# Schematic.net
KiCad netlist of a schematic drawn in EAGLE
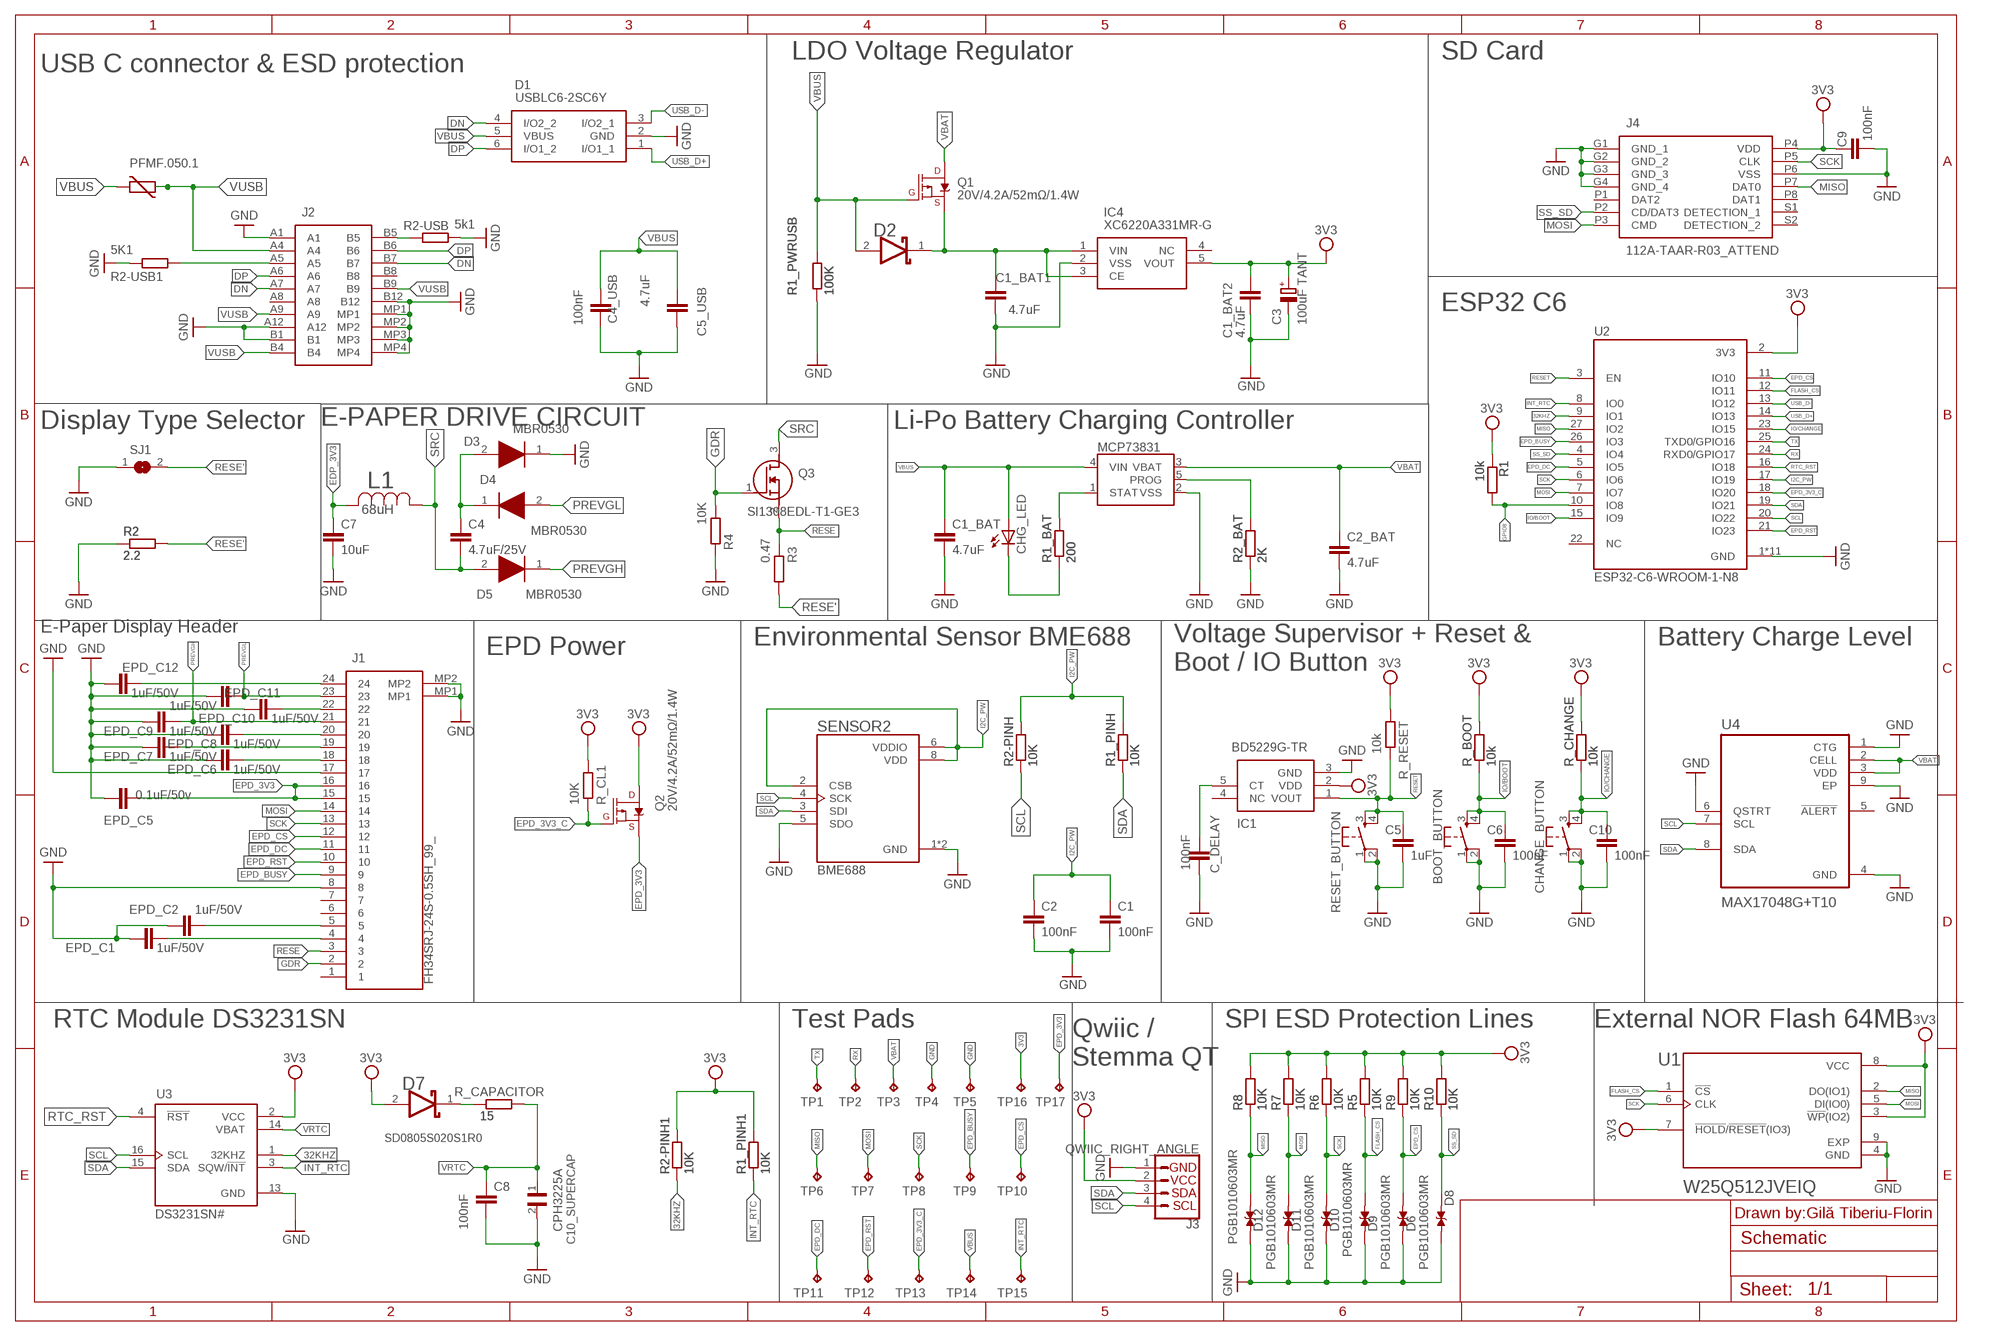
[diagram p0: schematic, sheet 1]

(export (version "E")
  (design (tool "Eeschema 10.0.6"))
  (components
    (comp (ref "BOOT_BUTTON")
      (value "BUTTON_CUSYOMV1")
      (footprint "eagle-import:MYBUTTON")
      (libsource (lib "eagle-import") (part "BUTTON_CUSYOMV1"))
    )
    (comp (ref "C1")
      (value "100nF")
      (footprint "eagle-import:EAGLE-LTSPICE_C0402")
      (libsource (lib "eagle-import") (part "EAGLE-LTSPICE_CC0402"))
    )
    (comp (ref "C1_BAT")
      (value "4.7uF")
      (footprint "eagle-import:EAGLE-LTSPICE_C0402")
      (libsource (lib "eagle-import") (part "EAGLE-LTSPICE_CC0402"))
    )
    (comp (ref "C1_BAT1")
      (value "4.7uF")
      (footprint "eagle-import:ESP32_WROVER_EAGLE-LTSPICE_C0402")
      (libsource (lib "eagle-import") (part "ESP32_WROVER_EAGLE-LTSPICE_CC0402"))
    )
    (comp (ref "C1_BAT2")
      (value "4.7uF")
      (footprint "eagle-import:ESP32_WROVER_EAGLE-LTSPICE_C0402")
      (libsource (lib "eagle-import") (part "ESP32_WROVER_EAGLE-LTSPICE_CC0402"))
    )
    (comp (ref "C2")
      (value "100nF")
      (footprint "eagle-import:EAGLE-LTSPICE_C0402")
      (libsource (lib "eagle-import") (part "EAGLE-LTSPICE_CC0402"))
    )
    (comp (ref "C2_BAT")
      (value "4.7uF")
      (footprint "eagle-import:EAGLE-LTSPICE_C0402")
      (libsource (lib "eagle-import") (part "EAGLE-LTSPICE_CC0402"))
    )
    (comp (ref "C3")
      (value "100uF TANT")
      (footprint "eagle-import:RCL_CT3528")
      (libsource (lib "eagle-import") (part "RCL_CPOL-EUCT3528"))
    )
    (comp (ref "C4")
      (value "4.7uF/25V")
      (footprint "eagle-import:EAGLE-LTSPICE_C0402")
      (libsource (lib "eagle-import") (part "EAGLE-LTSPICE_CC0402"))
    )
    (comp (ref "C4_USB")
      (value "100nF")
      (footprint "eagle-import:EAGLE-LTSPICE_C0402")
      (libsource (lib "eagle-import") (part "EAGLE-LTSPICE_CC0402"))
    )
    (comp (ref "C5")
      (value "1uF")
      (footprint "eagle-import:EAGLE-LTSPICE_C0402")
      (libsource (lib "eagle-import") (part "EAGLE-LTSPICE_CC0402"))
    )
    (comp (ref "C5_USB")
      (value "4.7uF")
      (footprint "eagle-import:EAGLE-LTSPICE_C0402")
      (libsource (lib "eagle-import") (part "EAGLE-LTSPICE_CC0402"))
    )
    (comp (ref "C6")
      (value "100nF")
      (footprint "eagle-import:EAGLE-LTSPICE_C0402")
      (libsource (lib "eagle-import") (part "EAGLE-LTSPICE_CC0402"))
    )
    (comp (ref "C7")
      (value "10uF")
      (footprint "eagle-import:EAGLE-LTSPICE_C0402")
      (libsource (lib "eagle-import") (part "EAGLE-LTSPICE_CC0402"))
    )
    (comp (ref "C8")
      (value "100nF")
      (footprint "eagle-import:EAGLE-LTSPICE_C0402")
      (libsource (lib "eagle-import") (part "EAGLE-LTSPICE_CC0402"))
    )
    (comp (ref "C9")
      (value "100nF")
      (footprint "eagle-import:EAGLE-LTSPICE_C0402")
      (libsource (lib "eagle-import") (part "EAGLE-LTSPICE_CC0402"))
    )
    (comp (ref "C10")
      (value "100nF")
      (footprint "eagle-import:EAGLE-LTSPICE_C0402")
      (libsource (lib "eagle-import") (part "EAGLE-LTSPICE_CC0402"))
    )
    (comp (ref "C11")
      (value "CPH3225A")
      (footprint "eagle-import:CAPCP3225X100N")
      (fields (field (name "MF") "Seiko Instruments"))
      (libsource (lib "eagle-import") (part "CPH3225A"))
    )
    (comp (ref "CHANGE_BUTTON")
      (value "BUTTON_CUSYOMV1")
      (footprint "eagle-import:MYBUTTON")
      (libsource (lib "eagle-import") (part "BUTTON_CUSYOMV1"))
    )
    (comp (ref "CHG_LED")
      (value "ADAFRUIT_LEDCHIP-LED0603")
      (footprint "eagle-import:ADAFRUIT_CHIP-LED0603")
      (libsource (lib "eagle-import") (part "ADAFRUIT_LEDCHIP-LED0603"))
    )
    (comp (ref "C_DELAY")
      (value "100nF")
      (footprint "eagle-import:EAGLE-LTSPICE_C0402")
      (libsource (lib "eagle-import") (part "EAGLE-LTSPICE_CC0402"))
    )
    (comp (ref "D1")
      (value "USBLC6-2SC6Y")
      (footprint "eagle-import:SOT95P280X145-6N")
      (fields (field (name "MF") "STMicroelectronics"))
      (libsource (lib "eagle-import") (part "USBLC6-2SC6Y"))
    )
    (comp (ref "D2")
      (value "ESP32_WROVER_AVX---SD0805S020S1R0_AVX_SD0805S020S1R0_0_0AVX_SD0805S020S1R0_0_0")
      (footprint "eagle-import:ESP32_WROVER_AVX---SD0805S020S1R0_AVX_SD0805S020S1R0_0")
      (fields
        (field (name "DIGIKEY_PART_NUMBER") "478-7800-1-ND")
        (field (name "MF") "AVX")
        (field (name "MOUSER_PART_NUMBER") "581-SD0805S020S1R0")
      )
      (libsource (lib "eagle-import") (part "ESP32_WROVER_AVX---SD0805S020S1R0_AVX_SD0805S020S1R0_0_0AVX_SD0805S020S1R0_0_0"))
    )
    (comp (ref "D3")
      (value "MBR0530")
      (footprint "eagle-import:SOD3716X135N")
      (fields (field (name "MF") "ON Semiconductor"))
      (libsource (lib "eagle-import") (part "MBR0530"))
    )
    (comp (ref "D4")
      (value "MBR0530")
      (footprint "eagle-import:SOD3716X135N")
      (fields (field (name "MF") "ON Semiconductor"))
      (libsource (lib "eagle-import") (part "MBR0530"))
    )
    (comp (ref "D5")
      (value "MBR0530")
      (footprint "eagle-import:SOD3716X135N")
      (fields (field (name "MF") "ON Semiconductor"))
      (libsource (lib "eagle-import") (part "MBR0530"))
    )
    (comp (ref "D6")
      (value "PGB1010603MR")
      (footprint "eagle-import:DIOC1608X36N")
      (fields (field (name "MF") "Littelfuse Inc."))
      (libsource (lib "eagle-import") (part "PGB1010603MR"))
    )
    (comp (ref "D7")
      (value "ESP32_WROVER_AVX---SD0805S020S1R0_AVX_SD0805S020S1R0_0_0AVX_SD0805S020S1R0_0_0")
      (footprint "eagle-import:ESP32_WROVER_AVX---SD0805S020S1R0_AVX_SD0805S020S1R0_0")
      (fields
        (field (name "DIGIKEY_PART_NUMBER") "478-7800-1-ND")
        (field (name "MF") "AVX")
        (field (name "MOUSER_PART_NUMBER") "581-SD0805S020S1R0")
      )
      (libsource (lib "eagle-import") (part "ESP32_WROVER_AVX---SD0805S020S1R0_AVX_SD0805S020S1R0_0_0AVX_SD0805S020S1R0_0_0"))
    )
    (comp (ref "D8")
      (value "PGB1010603MR")
      (footprint "eagle-import:DIOC1608X36N")
      (fields (field (name "MF") "Littelfuse Inc."))
      (libsource (lib "eagle-import") (part "PGB1010603MR"))
    )
    (comp (ref "D9")
      (value "PGB1010603MR")
      (footprint "eagle-import:DIOC1608X36N")
      (fields (field (name "MF") "Littelfuse Inc."))
      (libsource (lib "eagle-import") (part "PGB1010603MR"))
    )
    (comp (ref "D10")
      (value "PGB1010603MR")
      (footprint "eagle-import:DIOC1608X36N")
      (fields (field (name "MF") "Littelfuse Inc."))
      (libsource (lib "eagle-import") (part "PGB1010603MR"))
    )
    (comp (ref "D11")
      (value "PGB1010603MR")
      (footprint "eagle-import:DIOC1608X36N")
      (fields (field (name "MF") "Littelfuse Inc."))
      (libsource (lib "eagle-import") (part "PGB1010603MR"))
    )
    (comp (ref "D12")
      (value "PGB1010603MR")
      (footprint "eagle-import:DIOC1608X36N")
      (fields (field (name "MF") "Littelfuse Inc."))
      (libsource (lib "eagle-import") (part "PGB1010603MR"))
    )
    (comp (ref "EPD_C1")
      (value "1uF/50V")
      (footprint "eagle-import:EAGLE-LTSPICE_C0402")
      (libsource (lib "eagle-import") (part "EAGLE-LTSPICE_CC0402"))
    )
    (comp (ref "EPD_C2")
      (value "1uF/50V")
      (footprint "eagle-import:EAGLE-LTSPICE_C0402")
      (libsource (lib "eagle-import") (part "EAGLE-LTSPICE_CC0402"))
    )
    (comp (ref "EPD_C5")
      (value "0.1uF/50v")
      (footprint "eagle-import:EAGLE-LTSPICE_C0402")
      (libsource (lib "eagle-import") (part "EAGLE-LTSPICE_CC0402"))
    )
    (comp (ref "EPD_C6")
      (value "1uF/50V")
      (footprint "eagle-import:EAGLE-LTSPICE_C0402")
      (libsource (lib "eagle-import") (part "EAGLE-LTSPICE_CC0402"))
    )
    (comp (ref "EPD_C7")
      (value "1uF/50V")
      (footprint "eagle-import:EAGLE-LTSPICE_C0402")
      (libsource (lib "eagle-import") (part "EAGLE-LTSPICE_CC0402"))
    )
    (comp (ref "EPD_C8")
      (value "1uF/50V")
      (footprint "eagle-import:EAGLE-LTSPICE_C0402")
      (libsource (lib "eagle-import") (part "EAGLE-LTSPICE_CC0402"))
    )
    (comp (ref "EPD_C9")
      (value "1uF/50V")
      (footprint "eagle-import:EAGLE-LTSPICE_C0402")
      (libsource (lib "eagle-import") (part "EAGLE-LTSPICE_CC0402"))
    )
    (comp (ref "EPD_C10")
      (value "1uF/50V")
      (footprint "eagle-import:EAGLE-LTSPICE_C0402")
      (libsource (lib "eagle-import") (part "EAGLE-LTSPICE_CC0402"))
    )
    (comp (ref "EPD_C11")
      (value "1uF/50V")
      (footprint "eagle-import:EAGLE-LTSPICE_C0402")
      (libsource (lib "eagle-import") (part "EAGLE-LTSPICE_CC0402"))
    )
    (comp (ref "EPD_C12")
      (value "1uF/50V")
      (footprint "eagle-import:EAGLE-LTSPICE_C0402")
      (libsource (lib "eagle-import") (part "EAGLE-LTSPICE_CC0402"))
    )
    (comp (ref "IC1")
      (value "BD5229G-TR")
      (footprint "eagle-import:SOT95P280X125-5N")
      (fields (field (name "MOUSER_PART_NUMBER") "755-BD5229G-TR"))
      (libsource (lib "eagle-import") (part "BD5229G-TR"))
    )
    (comp (ref "IC4")
      (value "XC6220A331MR-G")
      (footprint "eagle-import:SOT95P280X120-5N")
      (fields (field (name "MOUSER_PART_NUMBER") "865-XC6220A331MR-G"))
      (libsource (lib "eagle-import") (part "XC6220A331MR-G"))
    )
    (comp (ref "J1")
      (value "FH34SRJ-24S-0.5SH_99_")
      (footprint "eagle-import:FH34SRJ24S05SH99")
      (fields
        (field (name "MANUFACTURER_PART_NUMBER") "FH34SRJ-24S-0.5SH(99)")
        (field (name "MOUSER_PART_NUMBER") "798-FH34SRJ24S05SH99")
      )
      (libsource (lib "eagle-import") (part "FH34SRJ-24S-0.5SH_99_"))
    )
    (comp (ref "J2")
      (value "SAMACSYS_PARTS_USB4110-GF-A")
      (footprint "eagle-import:SAMACSYS_PARTS_USB4110GFA")
      (fields
        (field (name "MANUFACTURER_PART_NUMBER") "USB4110-GF-A")
        (field (name "MOUSER_PART_NUMBER") "640-USB4110-GF-A")
      )
      (libsource (lib "eagle-import") (part "SAMACSYS_PARTS_USB4110-GF-A"))
    )
    (comp (ref "J3")
      (value "QWIIC_RIGHT_ANGLE")
      (footprint "eagle-import:JST04_1MM_RA")
      (libsource (lib "eagle-import") (part "QWIIC_CONNECTORJS-1MM"))
    )
    (comp (ref "J4")
      (value "112A-TAAR-R03_ATTEND")
      (footprint "eagle-import:112ATAARR03ATTEND")
      (fields (field (name "MANUFACTURER_PART_NUMBER") "112A-TAAR-R03 ATTEND"))
      (libsource (lib "eagle-import") (part "112A-TAAR-R03_ATTEND"))
    )
    (comp (ref "L1")
      (value "68uH")
      (footprint "eagle-import:IND_4828-WE-TPC_WRE")
      (fields
        (field (name "MANUFACTURER_PART_NUMBER") "744043680")
        (field (name "COPYRIGHT") "Copyright (C) 2024 Ultra Librarian. All rights reserved.")
      )
      (libsource (lib "eagle-import") (part "744043680IND_4828-WE-TPC_WRE"))
    )
    (comp (ref "MCP73831")
      (value "ESP32_WROVER_SPARKFUN-IC-POWER_MCP73831")
      (footprint "eagle-import:ESP32_WROVER_SPARKFUN-IC-POWER_SOT23-5")
      (libsource (lib "eagle-import") (part "ESP32_WROVER_SPARKFUN-IC-POWER_MCP73831"))
    )
    (comp (ref "PFMF.050.1")
      (value "ESP32C6_VARISTORCN1812")
      (footprint "eagle-import:ESP32C6_VARISTOR_CT_CN1812")
      (libsource (lib "eagle-import") (part "ESP32C6_VARISTORCN1812"))
    )
    (comp (ref "Q1")
      (value "20V/4.2A/52mΩ/1.4W")
      (footprint "eagle-import:ESP32_WROVER_SPARKFUN-DISCRETESEMI_SOT23-3")
      (libsource (lib "eagle-import") (part "ESP32_WROVER_SPARKFUN-DISCRETESEMI_MOSFET_PCH-DMG2305UX-7"))
    )
    (comp (ref "Q2")
      (value "20V/4.2A/52mΩ/1.4W")
      (footprint "eagle-import:ESP32_WROVER_SPARKFUN-DISCRETESEMI_SOT23-3")
      (libsource (lib "eagle-import") (part "ESP32_WROVER_SPARKFUN-DISCRETESEMI_MOSFET_PCH-DMG2305UX-7"))
    )
    (comp (ref "Q3")
      (value "SI1308EDL-T1-GE3")
      (footprint "eagle-import:SOT65P210X110-3N")
      (fields (field (name "MF") "Vishay Siliconix"))
      (libsource (lib "eagle-import") (part "SI1308EDL-T1-GE3"))
    )
    (comp (ref "R1")
      (value "10k")
      (footprint "eagle-import:ESP32_WROVER_EAGLE-LTSPICE_R0402")
      (libsource (lib "eagle-import") (part "ESP32_WROVER_EAGLE-LTSPICE_RR0402"))
    )
    (comp (ref "R1_BAT")
      (value "200")
      (footprint "eagle-import:ESP32_WROVER_EAGLE-LTSPICE_R0402")
      (libsource (lib "eagle-import") (part "ESP32_WROVER_EAGLE-LTSPICE_RR0402"))
    )
    (comp (ref "R1_PINH")
      (value "10K")
      (footprint "eagle-import:ESP32_WROVER_EAGLE-LTSPICE_R0402")
      (libsource (lib "eagle-import") (part "ESP32_WROVER_EAGLE-LTSPICE_RR0402"))
    )
    (comp (ref "R1_PINH1")
      (value "10K")
      (footprint "eagle-import:ESP32_WROVER_EAGLE-LTSPICE_R0402")
      (libsource (lib "eagle-import") (part "ESP32_WROVER_EAGLE-LTSPICE_RR0402"))
    )
    (comp (ref "R1_PWRUSB")
      (value "100K")
      (footprint "eagle-import:ESP32_WROVER_EAGLE-LTSPICE_R0402")
      (libsource (lib "eagle-import") (part "ESP32_WROVER_EAGLE-LTSPICE_RR0402"))
    )
    (comp (ref "R2")
      (value "2.2")
      (footprint "eagle-import:ESP32_WROVER_EAGLE-LTSPICE_R0402")
      (libsource (lib "eagle-import") (part "ESP32_WROVER_EAGLE-LTSPICE_RR0402"))
    )
    (comp (ref "R2-PINH")
      (value "10K")
      (footprint "eagle-import:ESP32_WROVER_EAGLE-LTSPICE_R0402")
      (libsource (lib "eagle-import") (part "ESP32_WROVER_EAGLE-LTSPICE_RR0402"))
    )
    (comp (ref "R2-PINH1")
      (value "10K")
      (footprint "eagle-import:ESP32_WROVER_EAGLE-LTSPICE_R0402")
      (libsource (lib "eagle-import") (part "ESP32_WROVER_EAGLE-LTSPICE_RR0402"))
    )
    (comp (ref "R2-USB")
      (value "5k1")
      (footprint "eagle-import:ESP32_WROVER_EAGLE-LTSPICE_R0402")
      (libsource (lib "eagle-import") (part "ESP32_WROVER_EAGLE-LTSPICE_RR0402"))
    )
    (comp (ref "R2-USB1")
      (value "5K1")
      (footprint "eagle-import:ESP32_WROVER_EAGLE-LTSPICE_R0402")
      (fields (field (name "SPICEPREFIX") "R2-USB1"))
      (libsource (lib "eagle-import") (part "ESP32_WROVER_EAGLE-LTSPICE_RR0402"))
    )
    (comp (ref "R2_BAT")
      (value "2K")
      (footprint "eagle-import:ESP32_WROVER_EAGLE-LTSPICE_R0402")
      (libsource (lib "eagle-import") (part "ESP32_WROVER_EAGLE-LTSPICE_RR0402"))
    )
    (comp (ref "R3")
      (value "0.47")
      (footprint "eagle-import:ESP32_WROVER_EAGLE-LTSPICE_R0402")
      (libsource (lib "eagle-import") (part "ESP32_WROVER_EAGLE-LTSPICE_RR0402"))
    )
    (comp (ref "R4")
      (value "10K")
      (footprint "eagle-import:ESP32_WROVER_EAGLE-LTSPICE_R0402")
      (libsource (lib "eagle-import") (part "ESP32_WROVER_EAGLE-LTSPICE_RR0402"))
    )
    (comp (ref "R5")
      (value "10K")
      (footprint "eagle-import:ESP32_WROVER_EAGLE-LTSPICE_R0402")
      (libsource (lib "eagle-import") (part "ESP32_WROVER_EAGLE-LTSPICE_RR0402"))
    )
    (comp (ref "R6")
      (value "10K")
      (footprint "eagle-import:ESP32_WROVER_EAGLE-LTSPICE_R0402")
      (libsource (lib "eagle-import") (part "ESP32_WROVER_EAGLE-LTSPICE_RR0402"))
    )
    (comp (ref "R7")
      (value "10K")
      (footprint "eagle-import:ESP32_WROVER_EAGLE-LTSPICE_R0402")
      (libsource (lib "eagle-import") (part "ESP32_WROVER_EAGLE-LTSPICE_RR0402"))
    )
    (comp (ref "R8")
      (value "10K")
      (footprint "eagle-import:ESP32_WROVER_EAGLE-LTSPICE_R0402")
      (libsource (lib "eagle-import") (part "ESP32_WROVER_EAGLE-LTSPICE_RR0402"))
    )
    (comp (ref "R9")
      (value "10K")
      (footprint "eagle-import:ESP32_WROVER_EAGLE-LTSPICE_R0402")
      (libsource (lib "eagle-import") (part "ESP32_WROVER_EAGLE-LTSPICE_RR0402"))
    )
    (comp (ref "R10")
      (value "10K")
      (footprint "eagle-import:ESP32_WROVER_EAGLE-LTSPICE_R0402")
      (libsource (lib "eagle-import") (part "ESP32_WROVER_EAGLE-LTSPICE_RR0402"))
    )
    (comp (ref "RESET_BUTTON")
      (value "BUTTON_CUSYOMV1")
      (footprint "eagle-import:MYBUTTON")
      (libsource (lib "eagle-import") (part "BUTTON_CUSYOMV1"))
    )
    (comp (ref "R_BOOT")
      (value "10k")
      (footprint "eagle-import:ESP32_WROVER_EAGLE-LTSPICE_R0402")
      (libsource (lib "eagle-import") (part "ESP32_WROVER_EAGLE-LTSPICE_RR0402"))
    )
    (comp (ref "R_CAPACITOR")
      (value "15")
      (footprint "eagle-import:ESP32_WROVER_EAGLE-LTSPICE_R0402")
      (libsource (lib "eagle-import") (part "ESP32_WROVER_EAGLE-LTSPICE_RR0402"))
    )
    (comp (ref "R_CHANGE")
      (value "10k")
      (footprint "eagle-import:ESP32_WROVER_EAGLE-LTSPICE_R0402")
      (libsource (lib "eagle-import") (part "ESP32_WROVER_EAGLE-LTSPICE_RR0402"))
    )
    (comp (ref "R_CL1")
      (value "10K")
      (footprint "eagle-import:ESP32_WROVER_EAGLE-LTSPICE_R0402")
      (libsource (lib "eagle-import") (part "ESP32_WROVER_EAGLE-LTSPICE_RR0402"))
    )
    (comp (ref "R_RESET")
      (value "10k")
      (footprint "eagle-import:ESP32_WROVER_EAGLE-LTSPICE_R0402")
      (libsource (lib "eagle-import") (part "ESP32_WROVER_EAGLE-LTSPICE_RR0402"))
    )
    (comp (ref "SENSOR2")
      (value "ESP32_WROVER_BME680_BME680")
      (footprint "eagle-import:ESP32_WROVER_BME680_PSON80P300X300X100-8N")
      (fields (field (name "MF") "Bosch Sensortec") (field (name "MP") "BME680"))
      (libsource (lib "eagle-import") (part "ESP32_WROVER_BME680_BME680"))
    )
    (comp (ref "SJ1") (value "SJ") (footprint "eagle-import:SJ") (libsource (lib "eagle-import") (part "SJ")))
    (comp (ref "TP1")
      (value "TPTP20R")
      (footprint "eagle-import:TP20R")
      (libsource (lib "eagle-import") (part "TPTP20R"))
    )
    (comp (ref "TP2")
      (value "TPTP20R")
      (footprint "eagle-import:TP20R")
      (libsource (lib "eagle-import") (part "TPTP20R"))
    )
    (comp (ref "TP3")
      (value "TPTP20R")
      (footprint "eagle-import:TP20R")
      (libsource (lib "eagle-import") (part "TPTP20R"))
    )
    (comp (ref "TP4")
      (value "TPTP20R")
      (footprint "eagle-import:TP20R")
      (libsource (lib "eagle-import") (part "TPTP20R"))
    )
    (comp (ref "TP5")
      (value "TPTP20R")
      (footprint "eagle-import:TP20R")
      (libsource (lib "eagle-import") (part "TPTP20R"))
    )
    (comp (ref "TP6")
      (value "TPTP20R")
      (footprint "eagle-import:TP20R")
      (libsource (lib "eagle-import") (part "TPTP20R"))
    )
    (comp (ref "TP7")
      (value "TPTP20R")
      (footprint "eagle-import:TP20R")
      (libsource (lib "eagle-import") (part "TPTP20R"))
    )
    (comp (ref "TP8")
      (value "TPTP20R")
      (footprint "eagle-import:TP20R")
      (libsource (lib "eagle-import") (part "TPTP20R"))
    )
    (comp (ref "TP9")
      (value "TPTP20R")
      (footprint "eagle-import:TP20R")
      (libsource (lib "eagle-import") (part "TPTP20R"))
    )
    (comp (ref "TP10")
      (value "TPTP20R")
      (footprint "eagle-import:TP20R")
      (libsource (lib "eagle-import") (part "TPTP20R"))
    )
    (comp (ref "TP11")
      (value "TPTP20R")
      (footprint "eagle-import:TP20R")
      (libsource (lib "eagle-import") (part "TPTP20R"))
    )
    (comp (ref "TP12")
      (value "TPTP20R")
      (footprint "eagle-import:TP20R")
      (libsource (lib "eagle-import") (part "TPTP20R"))
    )
    (comp (ref "TP13")
      (value "TPTP20R")
      (footprint "eagle-import:TP20R")
      (libsource (lib "eagle-import") (part "TPTP20R"))
    )
    (comp (ref "TP14")
      (value "TPTP20R")
      (footprint "eagle-import:TP20R")
      (libsource (lib "eagle-import") (part "TPTP20R"))
    )
    (comp (ref "TP15")
      (value "TPTP20R")
      (footprint "eagle-import:TP20R")
      (libsource (lib "eagle-import") (part "TPTP20R"))
    )
    (comp (ref "TP16")
      (value "TPTP20R")
      (footprint "eagle-import:TP20R")
      (libsource (lib "eagle-import") (part "TPTP20R"))
    )
    (comp (ref "TP17")
      (value "TPTP20R")
      (footprint "eagle-import:TP20R")
      (libsource (lib "eagle-import") (part "TPTP20R"))
    )
    (comp (ref "U1")
      (value "W25Q512JVEIQ")
      (footprint "eagle-import:SON127P600X800X80-9N")
      (fields (field (name "MF") "Winbond Electronics"))
      (libsource (lib "eagle-import") (part "W25Q512JVEIQ"))
    )
    (comp (ref "U2")
      (value "ESP32-C6-WROOM-1-N8")
      (footprint "eagle-import:XCVR_ESP32-C6-WROOM-1-N8")
      (fields (field (name "MF") "Espressif Systems"))
      (libsource (lib "eagle-import") (part "ESP32-C6-WROOM-1-N8"))
    )
    (comp (ref "U3")
      (value "DS3231SN#")
      (footprint "eagle-import:SOIC127P1032X265-16N")
      (fields (field (name "MF") "Analog Devices"))
      (libsource (lib "eagle-import") (part "DS3231SN#"))
    )
    (comp (ref "U4")
      (value "MAX17048G+T10")
      (footprint "eagle-import:SON50P200X200X80-9N")
      (fields (field (name "MF") "Analog Devices"))
      (libsource (lib "eagle-import") (part "MAX17048G+T10"))
    )
  )
  (nets
    (net (code "1") (name "3V3") (class "Default")
      (node (ref "C1_BAT2") (pin "1") (pinfunction "1_1") (pintype "passive"))
      (node (ref "C3") (pin "+") (pinfunction "+_+") (pintype "passive"))
      (node (ref "C9") (pin "2") (pinfunction "2_2") (pintype "passive"))
      (node (ref "D7") (pin "2") (pinfunction "ANODE_2") (pintype "bidirectional"))
      (node (ref "IC1") (pin "2") (pinfunction "VDD_2") (pintype "bidirectional"))
      (node (ref "IC4") (pin "5") (pinfunction "VOUT_5") (pintype "bidirectional"))
      (node (ref "J3") (pin "2") (pinfunction "2_2") (pintype "power_in"))
      (node (ref "J4") (pin "P4") (pinfunction "VDD_P4") (pintype "bidirectional"))
      (node (ref "Q2") (pin "3") (pinfunction "D_3") (pintype "bidirectional"))
      (node (ref "R1") (pin "1") (pinfunction "1_1") (pintype "passive"))
      (node (ref "R10") (pin "2") (pinfunction "2_2") (pintype "passive"))
      (node (ref "R1_PINH1") (pin "2") (pinfunction "2_2") (pintype "passive"))
      (node (ref "R2-PINH1") (pin "2") (pinfunction "2_2") (pintype "passive"))
      (node (ref "R5") (pin "2") (pinfunction "2_2") (pintype "passive"))
      (node (ref "R6") (pin "2") (pinfunction "2_2") (pintype "passive"))
      (node (ref "R7") (pin "2") (pinfunction "2_2") (pintype "passive"))
      (node (ref "R8") (pin "2") (pinfunction "2_2") (pintype "passive"))
      (node (ref "R9") (pin "2") (pinfunction "2_2") (pintype "passive"))
      (node (ref "R_BOOT") (pin "2") (pinfunction "2_2") (pintype "passive"))
      (node (ref "R_CHANGE") (pin "2") (pinfunction "2_2") (pintype "passive"))
      (node (ref "R_CL1") (pin "2") (pinfunction "2_2") (pintype "passive"))
      (node (ref "R_RESET") (pin "2") (pinfunction "2_2") (pintype "passive"))
      (node (ref "TP16") (pin "TP") (pinfunction "TP_TP") (pintype "input"))
      (node (ref "U1") (pin "3") (pinfunction "~{WP}(IO2)_3") (pintype "bidirectional"))
      (node (ref "U1") (pin "7") (pinfunction "~{HOLD}/~{RESET}(IO3)_7") (pintype "bidirectional"))
      (node (ref "U1") (pin "8") (pinfunction "VCC_8") (pintype "power_in"))
      (node (ref "U2") (pin "2") (pinfunction "3V3_2") (pintype "power_in"))
      (node (ref "U3") (pin "2") (pinfunction "VCC_2") (pintype "power_in"))
    )
    (net (code "2") (name "32KHZ") (class "Default")
      (node (ref "R2-PINH1") (pin "1") (pinfunction "1_1") (pintype "passive"))
      (node (ref "U2") (pin "9") (pinfunction "IO1_9") (pintype "bidirectional"))
      (node (ref "U3") (pin "1") (pinfunction "32KHZ_1") (pintype "output"))
    )
    (net (code "3") (name "DN") (class "Default")
      (node (ref "D1") (pin "4") (pinfunction "I/O2_2_4") (pintype "bidirectional"))
      (node (ref "J2") (pin "A7") (pinfunction "A7_A7") (pintype "bidirectional"))
      (node (ref "J2") (pin "B7") (pinfunction "B7_B7") (pintype "bidirectional"))
    )
    (net (code "4") (name "DP") (class "Default")
      (node (ref "D1") (pin "6") (pinfunction "I/O1_2_6") (pintype "bidirectional"))
      (node (ref "J2") (pin "A6") (pinfunction "A6_A6") (pintype "bidirectional"))
      (node (ref "J2") (pin "B6") (pinfunction "B6_B6") (pintype "bidirectional"))
    )
    (net (code "5") (name "EDP_3V3") (class "Default")
      (node (ref "C7") (pin "1") (pinfunction "1_1") (pintype "passive"))
      (node (ref "L1") (pin "2") (pinfunction "2_2") (pintype "passive"))
    )
    (net (code "6") (name "EPD_3V3") (class "Default")
      (node (ref "EPD_C5") (pin "2") (pinfunction "2_2") (pintype "passive"))
      (node (ref "J1") (pin "15") (pinfunction "15_15") (pintype "bidirectional"))
      (node (ref "J1") (pin "16") (pinfunction "16_16") (pintype "bidirectional"))
      (node (ref "Q2") (pin "2") (pinfunction "S_2") (pintype "bidirectional"))
      (node (ref "TP17") (pin "TP") (pinfunction "TP_TP") (pintype "input"))
    )
    (net (code "7") (name "EPD_3V3_C") (class "Default")
      (node (ref "Q2") (pin "1") (pinfunction "G_1") (pintype "bidirectional"))
      (node (ref "R_CL1") (pin "1") (pinfunction "1_1") (pintype "passive"))
      (node (ref "TP13") (pin "TP") (pinfunction "TP_TP") (pintype "input"))
      (node (ref "U2") (pin "18") (pinfunction "IO20_18") (pintype "bidirectional"))
    )
    (net (code "8") (name "EPD_BUSY") (class "Default")
      (node (ref "J1") (pin "9") (pinfunction "9_9") (pintype "bidirectional"))
      (node (ref "TP9") (pin "TP") (pinfunction "TP_TP") (pintype "input"))
      (node (ref "U2") (pin "26") (pinfunction "IO3_26") (pintype "bidirectional"))
    )
    (net (code "9") (name "EPD_CS") (class "Default")
      (node (ref "D6") (pin "2") (pinfunction "2_2") (pintype "passive"))
      (node (ref "J1") (pin "12") (pinfunction "12_12") (pintype "bidirectional"))
      (node (ref "R9") (pin "1") (pinfunction "1_1") (pintype "passive"))
      (node (ref "TP10") (pin "TP") (pinfunction "TP_TP") (pintype "input"))
      (node (ref "U2") (pin "11") (pinfunction "IO10_11") (pintype "bidirectional"))
    )
    (net (code "10") (name "EPD_DC") (class "Default")
      (node (ref "J1") (pin "11") (pinfunction "11_11") (pintype "bidirectional"))
      (node (ref "TP11") (pin "TP") (pinfunction "TP_TP") (pintype "input"))
      (node (ref "U2") (pin "5") (pinfunction "IO5_5") (pintype "bidirectional"))
    )
    (net (code "11") (name "EPD_RST") (class "Default")
      (node (ref "J1") (pin "10") (pinfunction "10_10") (pintype "bidirectional"))
      (node (ref "TP12") (pin "TP") (pinfunction "TP_TP") (pintype "input"))
      (node (ref "U2") (pin "21") (pinfunction "IO23_21") (pintype "bidirectional"))
    )
    (net (code "12") (name "FLASH_CS") (class "Default")
      (node (ref "D9") (pin "2") (pinfunction "2_2") (pintype "passive"))
      (node (ref "R5") (pin "1") (pinfunction "1_1") (pintype "passive"))
      (node (ref "U1") (pin "1") (pinfunction "~{CS}_1") (pintype "input"))
      (node (ref "U2") (pin "12") (pinfunction "IO11_12") (pintype "bidirectional"))
    )
    (net (code "13") (name "GDR") (class "Default")
      (node (ref "J1") (pin "2") (pinfunction "2_2") (pintype "bidirectional"))
      (node (ref "Q3") (pin "1") (pinfunction "G_1") (pintype "bidirectional"))
      (node (ref "R4") (pin "2") (pinfunction "2_2") (pintype "passive"))
    )
    (net (code "14") (name "GND") (class "Default")
      (node (ref "BOOT_BUTTON") (pin "1") (pinfunction "1_1") (pintype "passive"))
      (node (ref "BOOT_BUTTON") (pin "2") (pinfunction "2_2") (pintype "passive"))
      (node (ref "C1") (pin "2") (pinfunction "2_2") (pintype "passive"))
      (node (ref "C10") (pin "2") (pinfunction "2_2") (pintype "passive"))
      (node (ref "C11") (pin "2") (pinfunction "2_2") (pintype "passive"))
      (node (ref "C1_BAT") (pin "2") (pinfunction "2_2") (pintype "passive"))
      (node (ref "C1_BAT1") (pin "2") (pinfunction "2_2") (pintype "passive"))
      (node (ref "C1_BAT2") (pin "2") (pinfunction "2_2") (pintype "passive"))
      (node (ref "C2") (pin "2") (pinfunction "2_2") (pintype "passive"))
      (node (ref "C2_BAT") (pin "2") (pinfunction "2_2") (pintype "passive"))
      (node (ref "C3") (pin "-") (pinfunction "-_-") (pintype "passive"))
      (node (ref "C4_USB") (pin "2") (pinfunction "2_2") (pintype "passive"))
      (node (ref "C5") (pin "2") (pinfunction "2_2") (pintype "passive"))
      (node (ref "C5_USB") (pin "2") (pinfunction "2_2") (pintype "passive"))
      (node (ref "C6") (pin "2") (pinfunction "2_2") (pintype "passive"))
      (node (ref "C7") (pin "2") (pinfunction "2_2") (pintype "passive"))
      (node (ref "C8") (pin "2") (pinfunction "2_2") (pintype "passive"))
      (node (ref "C9") (pin "1") (pinfunction "1_1") (pintype "passive"))
      (node (ref "CHANGE_BUTTON") (pin "1") (pinfunction "1_1") (pintype "passive"))
      (node (ref "CHANGE_BUTTON") (pin "2") (pinfunction "2_2") (pintype "passive"))
      (node (ref "C_DELAY") (pin "2") (pinfunction "2_2") (pintype "passive"))
      (node (ref "D1") (pin "2") (pinfunction "GND_2") (pintype "bidirectional"))
      (node (ref "D10") (pin "1") (pinfunction "1_1") (pintype "passive"))
      (node (ref "D11") (pin "1") (pinfunction "1_1") (pintype "passive"))
      (node (ref "D12") (pin "1") (pinfunction "1_1") (pintype "passive"))
      (node (ref "D3") (pin "1") (pinfunction "K_1") (pintype "bidirectional"))
      (node (ref "D6") (pin "1") (pinfunction "1_1") (pintype "passive"))
      (node (ref "D8") (pin "1") (pinfunction "1_1") (pintype "passive"))
      (node (ref "D9") (pin "1") (pinfunction "1_1") (pintype "passive"))
      (node (ref "EPD_C1") (pin "1") (pinfunction "1_1") (pintype "passive"))
      (node (ref "EPD_C10") (pin "1") (pinfunction "1_1") (pintype "passive"))
      (node (ref "EPD_C11") (pin "1") (pinfunction "1_1") (pintype "passive"))
      (node (ref "EPD_C12") (pin "1") (pinfunction "1_1") (pintype "passive"))
      (node (ref "EPD_C2") (pin "1") (pinfunction "1_1") (pintype "passive"))
      (node (ref "EPD_C5") (pin "1") (pinfunction "1_1") (pintype "passive"))
      (node (ref "EPD_C6") (pin "1") (pinfunction "1_1") (pintype "passive"))
      (node (ref "EPD_C7") (pin "1") (pinfunction "1_1") (pintype "passive"))
      (node (ref "EPD_C8") (pin "1") (pinfunction "1_1") (pintype "passive"))
      (node (ref "EPD_C9") (pin "1") (pinfunction "1_1") (pintype "passive"))
      (node (ref "IC1") (pin "3") (pinfunction "GND_3") (pintype "bidirectional"))
      (node (ref "IC4") (pin "2") (pinfunction "VSS_2") (pintype "bidirectional"))
      (node (ref "J1") (pin "17") (pinfunction "17_17") (pintype "bidirectional"))
      (node (ref "J1") (pin "8") (pinfunction "8_8") (pintype "bidirectional"))
      (node (ref "J1") (pin "MP1") (pinfunction "MP1_MP1") (pintype "bidirectional"))
      (node (ref "J1") (pin "MP2") (pinfunction "MP2_MP2") (pintype "bidirectional"))
      (node (ref "J2") (pin "A1") (pinfunction "A1_A1") (pintype "bidirectional"))
      (node (ref "J2") (pin "A12") (pinfunction "A12_A12") (pintype "bidirectional"))
      (node (ref "J2") (pin "B1") (pinfunction "B1_B1") (pintype "bidirectional"))
      (node (ref "J2") (pin "B12") (pinfunction "B12_B12") (pintype "bidirectional"))
      (node (ref "J2") (pin "MP1") (pinfunction "MP1_MP1") (pintype "bidirectional"))
      (node (ref "J2") (pin "MP2") (pinfunction "MP2_MP2") (pintype "bidirectional"))
      (node (ref "J2") (pin "MP3") (pinfunction "MP3_MP3") (pintype "bidirectional"))
      (node (ref "J2") (pin "MP4") (pinfunction "MP4_MP4") (pintype "bidirectional"))
      (node (ref "J3") (pin "1") (pinfunction "1_1") (pintype "power_in"))
      (node (ref "J4") (pin "G1") (pinfunction "GND_1_G1") (pintype "bidirectional"))
      (node (ref "J4") (pin "G2") (pinfunction "GND_2_G2") (pintype "bidirectional"))
      (node (ref "J4") (pin "G3") (pinfunction "GND_3_G3") (pintype "bidirectional"))
      (node (ref "J4") (pin "G4") (pinfunction "GND_4_G4") (pintype "bidirectional"))
      (node (ref "J4") (pin "P6") (pinfunction "VSS_P6") (pintype "bidirectional"))
      (node (ref "MCP73831") (pin "2") (pinfunction "VSS_2") (pintype "power_in"))
      (node (ref "R1_PWRUSB") (pin "1") (pinfunction "1_1") (pintype "passive"))
      (node (ref "R2") (pin "1") (pinfunction "1_1") (pintype "passive"))
      (node (ref "R2-USB") (pin "2") (pinfunction "2_2") (pintype "passive"))
      (node (ref "R2-USB1") (pin "1") (pinfunction "1_1") (pintype "passive"))
      (node (ref "R2_BAT") (pin "1") (pinfunction "1_1") (pintype "passive"))
      (node (ref "R4") (pin "1") (pinfunction "1_1") (pintype "passive"))
      (node (ref "RESET_BUTTON") (pin "1") (pinfunction "1_1") (pintype "passive"))
      (node (ref "RESET_BUTTON") (pin "2") (pinfunction "2_2") (pintype "passive"))
      (node (ref "SENSOR2") (pin "1") (pinfunction "GND_1") (pintype "power_in"))
      (node (ref "SENSOR2") (pin "5") (pinfunction "SDO_5") (pintype "bidirectional"))
      (node (ref "SENSOR2") (pin "7") (pinfunction "GND_7") (pintype "power_in"))
      (node (ref "SJ1") (pin "1") (pinfunction "1_1") (pintype "passive"))
      (node (ref "TP4") (pin "TP") (pinfunction "TP_TP") (pintype "input"))
      (node (ref "TP5") (pin "TP") (pinfunction "TP_TP") (pintype "input"))
      (node (ref "U1") (pin "4") (pinfunction "GND_4") (pintype "power_in"))
      (node (ref "U1") (pin "9") (pinfunction "EXP_9") (pintype "passive"))
      (node (ref "U2") (pin "1") (pinfunction "GND_1") (pintype "power_in"))
      (node (ref "U2") (pin "28") (pinfunction "GND_28") (pintype "power_in"))
      (node (ref "U2") (pin "29_1") (pinfunction "GND_29_1") (pintype "power_in"))
      (node (ref "U2") (pin "29_2") (pinfunction "GND_29_2") (pintype "power_in"))
      (node (ref "U2") (pin "29_3") (pinfunction "GND_29_3") (pintype "power_in"))
      (node (ref "U2") (pin "29_4") (pinfunction "GND_29_4") (pintype "power_in"))
      (node (ref "U2") (pin "29_5") (pinfunction "GND_29_5") (pintype "power_in"))
      (node (ref "U2") (pin "29_6") (pinfunction "GND_29_6") (pintype "power_in"))
      (node (ref "U2") (pin "29_7") (pinfunction "GND_29_7") (pintype "power_in"))
      (node (ref "U2") (pin "29_8") (pinfunction "GND_29_8") (pintype "power_in"))
      (node (ref "U2") (pin "29_9") (pinfunction "GND_29_9") (pintype "power_in"))
      (node (ref "U3") (pin "13") (pinfunction "GND_13") (pintype "power_in"))
      (node (ref "U4") (pin "1") (pinfunction "CTG_1") (pintype "power_in"))
      (node (ref "U4") (pin "4") (pinfunction "GND_4") (pintype "power_in"))
      (node (ref "U4") (pin "6") (pinfunction "QSTRT_6") (pintype "input"))
      (node (ref "U4") (pin "9") (pinfunction "EP_9") (pintype "power_in"))
    )
    (net (code "15") (name "GPIO8") (class "Default")
      (node (ref "R1") (pin "2") (pinfunction "2_2") (pintype "passive"))
      (node (ref "U2") (pin "10") (pinfunction "IO8_10") (pintype "bidirectional"))
    )
    (net (code "16") (name "I2C_PW") (class "Default")
      (node (ref "C1") (pin "1") (pinfunction "1_1") (pintype "passive"))
      (node (ref "C2") (pin "1") (pinfunction "1_1") (pintype "passive"))
      (node (ref "R1_PINH") (pin "2") (pinfunction "2_2") (pintype "passive"))
      (node (ref "R2-PINH") (pin "2") (pinfunction "2_2") (pintype "passive"))
      (node (ref "SENSOR2") (pin "2") (pinfunction "CSB_2") (pintype "input"))
      (node (ref "SENSOR2") (pin "6") (pinfunction "VDDIO_6") (pintype "power_in"))
      (node (ref "SENSOR2") (pin "8") (pinfunction "VDD_8") (pintype "power_in"))
      (node (ref "U2") (pin "17") (pinfunction "IO19_17") (pintype "bidirectional"))
    )
    (net (code "17") (name "INT_RTC") (class "Default")
      (node (ref "R1_PINH1") (pin "1") (pinfunction "1_1") (pintype "passive"))
      (node (ref "TP15") (pin "TP") (pinfunction "TP_TP") (pintype "input"))
      (node (ref "U2") (pin "8") (pinfunction "IO0_8") (pintype "bidirectional"))
      (node (ref "U3") (pin "3") (pinfunction "SQW/~{INT}_3") (pintype "output"))
    )
    (net (code "18") (name "IO{slash}BOOT") (class "Default")
      (node (ref "BOOT_BUTTON") (pin "3") (pinfunction "3_3") (pintype "passive"))
      (node (ref "BOOT_BUTTON") (pin "4") (pinfunction "4_4") (pintype "passive"))
      (node (ref "C6") (pin "1") (pinfunction "1_1") (pintype "passive"))
      (node (ref "R_BOOT") (pin "1") (pinfunction "1_1") (pintype "passive"))
      (node (ref "U2") (pin "15") (pinfunction "IO9_15") (pintype "bidirectional"))
    )
    (net (code "19") (name "IO{slash}CHANGE") (class "Default")
      (node (ref "C10") (pin "1") (pinfunction "1_1") (pintype "passive"))
      (node (ref "CHANGE_BUTTON") (pin "3") (pinfunction "3_3") (pintype "passive"))
      (node (ref "CHANGE_BUTTON") (pin "4") (pinfunction "4_4") (pintype "passive"))
      (node (ref "R_CHANGE") (pin "1") (pinfunction "1_1") (pintype "passive"))
      (node (ref "U2") (pin "23") (pinfunction "IO15_23") (pintype "bidirectional"))
    )
    (net (code "20") (name "MISO") (class "Default")
      (node (ref "D12") (pin "2") (pinfunction "2_2") (pintype "passive"))
      (node (ref "J4") (pin "P7") (pinfunction "DAT0_P7") (pintype "bidirectional"))
      (node (ref "R8") (pin "1") (pinfunction "1_1") (pintype "passive"))
      (node (ref "TP6") (pin "TP") (pinfunction "TP_TP") (pintype "input"))
      (node (ref "U1") (pin "2") (pinfunction "DO(IO1)_2") (pintype "bidirectional"))
      (node (ref "U2") (pin "27") (pinfunction "IO2_27") (pintype "bidirectional"))
    )
    (net (code "21") (name "MOSI") (class "Default")
      (node (ref "D11") (pin "2") (pinfunction "2_2") (pintype "passive"))
      (node (ref "J1") (pin "14") (pinfunction "14_14") (pintype "bidirectional"))
      (node (ref "J4") (pin "P3") (pinfunction "CMD_P3") (pintype "bidirectional"))
      (node (ref "R7") (pin "1") (pinfunction "1_1") (pintype "passive"))
      (node (ref "TP7") (pin "TP") (pinfunction "TP_TP") (pintype "input"))
      (node (ref "U1") (pin "5") (pinfunction "DI(IO0)_5") (pintype "bidirectional"))
      (node (ref "U2") (pin "7") (pinfunction "IO7_7") (pintype "bidirectional"))
    )
    (net (code "22") (name "Net-(CHG_LED-PadC)") (class "Default")
      (node (ref "CHG_LED") (pin "C") (pinfunction "C_C") (pintype "passive"))
      (node (ref "R1_BAT") (pin "1") (pinfunction "1_1") (pintype "passive"))
    )
    (net (code "23") (name "Net-(D2-CATHODE)") (class "Default")
      (node (ref "C1_BAT1") (pin "1") (pinfunction "1_1") (pintype "passive"))
      (node (ref "D2") (pin "1") (pinfunction "CATHODE_1") (pintype "bidirectional"))
      (node (ref "IC4") (pin "1") (pinfunction "VIN_1") (pintype "bidirectional"))
      (node (ref "IC4") (pin "3") (pinfunction "CE_3") (pintype "bidirectional"))
      (node (ref "Q1") (pin "2") (pinfunction "S_2") (pintype "bidirectional"))
    )
    (net (code "24") (name "Net-(D3-A)") (class "Default")
      (node (ref "C4") (pin "1") (pinfunction "1_1") (pintype "passive"))
      (node (ref "D3") (pin "2") (pinfunction "A_2") (pintype "bidirectional"))
      (node (ref "D4") (pin "1") (pinfunction "K_1") (pintype "bidirectional"))
    )
    (net (code "25") (name "Net-(D7-CATHODE)") (class "Default")
      (node (ref "D7") (pin "1") (pinfunction "CATHODE_1") (pintype "bidirectional"))
      (node (ref "R_CAPACITOR") (pin "1") (pinfunction "1_1") (pintype "passive"))
    )
    (net (code "26") (name "Net-(EPD_C1-Pad2)") (class "Default")
      (node (ref "EPD_C1") (pin "2") (pinfunction "2_2") (pintype "passive"))
      (node (ref "J1") (pin "4") (pinfunction "4_4") (pintype "bidirectional"))
    )
    (net (code "27") (name "Net-(EPD_C2-Pad2)") (class "Default")
      (node (ref "EPD_C2") (pin "2") (pinfunction "2_2") (pintype "passive"))
      (node (ref "J1") (pin "5") (pinfunction "5_5") (pintype "bidirectional"))
    )
    (net (code "28") (name "Net-(EPD_C6-Pad2)") (class "Default")
      (node (ref "EPD_C6") (pin "2") (pinfunction "2_2") (pintype "passive"))
      (node (ref "J1") (pin "18") (pinfunction "18_18") (pintype "bidirectional"))
    )
    (net (code "29") (name "Net-(EPD_C7-Pad2)") (class "Default")
      (node (ref "EPD_C7") (pin "2") (pinfunction "2_2") (pintype "passive"))
      (node (ref "J1") (pin "19") (pinfunction "19_19") (pintype "bidirectional"))
    )
    (net (code "30") (name "Net-(EPD_C8-Pad2)") (class "Default")
      (node (ref "EPD_C8") (pin "2") (pinfunction "2_2") (pintype "passive"))
      (node (ref "J1") (pin "20") (pinfunction "20_20") (pintype "bidirectional"))
    )
    (net (code "31") (name "Net-(EPD_C10-Pad2)") (class "Default")
      (node (ref "EPD_C10") (pin "2") (pinfunction "2_2") (pintype "passive"))
      (node (ref "J1") (pin "22") (pinfunction "22_22") (pintype "bidirectional"))
    )
    (net (code "32") (name "Net-(EPD_C12-Pad2)") (class "Default")
      (node (ref "EPD_C12") (pin "2") (pinfunction "2_2") (pintype "passive"))
      (node (ref "J1") (pin "24") (pinfunction "24_24") (pintype "bidirectional"))
    )
    (net (code "33") (name "Net-(IC1-CT)") (class "Default")
      (node (ref "C_DELAY") (pin "1") (pinfunction "1_1") (pintype "passive"))
      (node (ref "IC1") (pin "5") (pinfunction "CT_5") (pintype "bidirectional"))
    )
    (net (code "34") (name "Net-(J2-PadA5)") (class "Default")
      (node (ref "J2") (pin "A5") (pinfunction "A5_A5") (pintype "bidirectional"))
      (node (ref "R2-USB1") (pin "2") (pinfunction "2_2") (pintype "passive"))
    )
    (net (code "35") (name "Net-(J2-PadB5)") (class "Default")
      (node (ref "J2") (pin "B5") (pinfunction "B5_B5") (pintype "bidirectional"))
      (node (ref "R2-USB") (pin "1") (pinfunction "1_1") (pintype "passive"))
    )
    (net (code "36") (name "Net-(MCP73831-PROG)") (class "Default")
      (node (ref "MCP73831") (pin "5") (pinfunction "PROG_5") (pintype "input"))
      (node (ref "R2_BAT") (pin "2") (pinfunction "2_2") (pintype "passive"))
    )
    (net (code "37") (name "Net-(MCP73831-STAT)") (class "Default")
      (node (ref "MCP73831") (pin "1") (pinfunction "STAT_1") (pintype "output"))
      (node (ref "R1_BAT") (pin "2") (pinfunction "2_2") (pintype "passive"))
    )
    (net (code "38") (name "PREVGH") (class "Default")
      (node (ref "D5") (pin "1") (pinfunction "K_1") (pintype "bidirectional"))
      (node (ref "EPD_C9") (pin "2") (pinfunction "2_2") (pintype "passive"))
      (node (ref "J1") (pin "21") (pinfunction "21_21") (pintype "bidirectional"))
    )
    (net (code "39") (name "PREVGL") (class "Default")
      (node (ref "D4") (pin "2") (pinfunction "A_2") (pintype "bidirectional"))
      (node (ref "EPD_C11") (pin "2") (pinfunction "2_2") (pintype "passive"))
      (node (ref "J1") (pin "23") (pinfunction "23_23") (pintype "bidirectional"))
    )
    (net (code "40") (name "RESE") (class "Default")
      (node (ref "J1") (pin "3") (pinfunction "3_3") (pintype "bidirectional"))
      (node (ref "Q3") (pin "2") (pinfunction "S_2") (pintype "bidirectional"))
      (node (ref "R3") (pin "2") (pinfunction "2_2") (pintype "passive"))
    )
    (net (code "41") (name "RESE'") (class "Default")
      (node (ref "R2") (pin "2") (pinfunction "2_2") (pintype "passive"))
      (node (ref "R3") (pin "1") (pinfunction "1_1") (pintype "passive"))
      (node (ref "SJ1") (pin "2") (pinfunction "2_2") (pintype "passive"))
    )
    (net (code "42") (name "RESET") (class "Default")
      (node (ref "C5") (pin "1") (pinfunction "1_1") (pintype "passive"))
      (node (ref "IC1") (pin "1") (pinfunction "VOUT_1") (pintype "bidirectional"))
      (node (ref "RESET_BUTTON") (pin "3") (pinfunction "3_3") (pintype "passive"))
      (node (ref "RESET_BUTTON") (pin "4") (pinfunction "4_4") (pintype "passive"))
      (node (ref "R_RESET") (pin "1") (pinfunction "1_1") (pintype "passive"))
      (node (ref "U2") (pin "3") (pinfunction "EN_3") (pintype "input"))
    )
    (net (code "43") (name "RTC_RST") (class "Default")
      (node (ref "U2") (pin "16") (pinfunction "IO18_16") (pintype "bidirectional"))
      (node (ref "U3") (pin "4") (pinfunction "~{RST}_4") (pintype "input"))
    )
    (net (code "44") (name "RX") (class "Default")
      (node (ref "TP2") (pin "TP") (pinfunction "TP_TP") (pintype "input"))
      (node (ref "U2") (pin "24") (pinfunction "RXD0/GPIO17_24") (pintype "bidirectional"))
    )
    (net (code "45") (name "SCK") (class "Default")
      (node (ref "D10") (pin "2") (pinfunction "2_2") (pintype "passive"))
      (node (ref "J1") (pin "13") (pinfunction "13_13") (pintype "bidirectional"))
      (node (ref "J4") (pin "P5") (pinfunction "CLK_P5") (pintype "bidirectional"))
      (node (ref "R6") (pin "1") (pinfunction "1_1") (pintype "passive"))
      (node (ref "TP8") (pin "TP") (pinfunction "TP_TP") (pintype "input"))
      (node (ref "U1") (pin "6") (pinfunction "CLK_6") (pintype "input"))
      (node (ref "U2") (pin "6") (pinfunction "IO6_6") (pintype "bidirectional"))
    )
    (net (code "46") (name "SCL") (class "Default")
      (node (ref "J3") (pin "4") (pinfunction "4_4") (pintype "passive"))
      (node (ref "R2-PINH") (pin "1") (pinfunction "1_1") (pintype "passive"))
      (node (ref "SENSOR2") (pin "4") (pinfunction "SCK_4") (pintype "input"))
      (node (ref "U2") (pin "20") (pinfunction "IO22_20") (pintype "bidirectional"))
      (node (ref "U3") (pin "16") (pinfunction "SCL_16") (pintype "input"))
      (node (ref "U4") (pin "7") (pinfunction "SCL_7") (pintype "input"))
    )
    (net (code "47") (name "SDA") (class "Default")
      (node (ref "J3") (pin "3") (pinfunction "3_3") (pintype "passive"))
      (node (ref "R1_PINH") (pin "1") (pinfunction "1_1") (pintype "passive"))
      (node (ref "SENSOR2") (pin "3") (pinfunction "SDI_3") (pintype "bidirectional"))
      (node (ref "U2") (pin "19") (pinfunction "IO21_19") (pintype "bidirectional"))
      (node (ref "U3") (pin "15") (pinfunction "SDA_15") (pintype "bidirectional"))
      (node (ref "U4") (pin "8") (pinfunction "SDA_8") (pintype "bidirectional"))
    )
    (net (code "48") (name "SRC") (class "Default")
      (node (ref "C4") (pin "2") (pinfunction "2_2") (pintype "passive"))
      (node (ref "D5") (pin "2") (pinfunction "A_2") (pintype "bidirectional"))
      (node (ref "L1") (pin "1") (pinfunction "1_1") (pintype "passive"))
      (node (ref "Q3") (pin "3") (pinfunction "D_3") (pintype "bidirectional"))
    )
    (net (code "49") (name "SS_SD") (class "Default")
      (node (ref "D8") (pin "2") (pinfunction "2_2") (pintype "passive"))
      (node (ref "J4") (pin "P2") (pinfunction "CD/DAT3_P2") (pintype "bidirectional"))
      (node (ref "R10") (pin "1") (pinfunction "1_1") (pintype "passive"))
      (node (ref "U2") (pin "4") (pinfunction "IO4_4") (pintype "bidirectional"))
    )
    (net (code "50") (name "TX") (class "Default")
      (node (ref "TP1") (pin "TP") (pinfunction "TP_TP") (pintype "input"))
      (node (ref "U2") (pin "25") (pinfunction "TXD0/GPIO16_25") (pintype "bidirectional"))
    )
    (net (code "51") (name "USB_D+") (class "Default")
      (node (ref "D1") (pin "1") (pinfunction "I/O1_1_1") (pintype "bidirectional"))
      (node (ref "U2") (pin "14") (pinfunction "IO13_14") (pintype "bidirectional"))
    )
    (net (code "52") (name "USB_D-") (class "Default")
      (node (ref "D1") (pin "3") (pinfunction "I/O2_1_3") (pintype "bidirectional"))
      (node (ref "U2") (pin "13") (pinfunction "IO12_13") (pintype "bidirectional"))
    )
    (net (code "53") (name "VBAT") (class "Default")
      (node (ref "C2_BAT") (pin "1") (pinfunction "1_1") (pintype "passive"))
      (node (ref "MCP73831") (pin "3") (pinfunction "VBAT_3") (pintype "power_in"))
      (node (ref "Q1") (pin "3") (pinfunction "D_3") (pintype "bidirectional"))
      (node (ref "TP3") (pin "TP") (pinfunction "TP_TP") (pintype "input"))
      (node (ref "U4") (pin "2") (pinfunction "CELL_2") (pintype "power_in"))
      (node (ref "U4") (pin "3") (pinfunction "VDD_3") (pintype "power_in"))
    )
    (net (code "54") (name "VBUS") (class "Default")
      (node (ref "C1_BAT") (pin "1") (pinfunction "1_1") (pintype "passive"))
      (node (ref "C4_USB") (pin "1") (pinfunction "1_1") (pintype "passive"))
      (node (ref "C5_USB") (pin "1") (pinfunction "1_1") (pintype "passive"))
      (node (ref "CHG_LED") (pin "A") (pinfunction "A_A") (pintype "passive"))
      (node (ref "D1") (pin "5") (pinfunction "VBUS_5") (pintype "bidirectional"))
      (node (ref "D2") (pin "2") (pinfunction "ANODE_2") (pintype "bidirectional"))
      (node (ref "MCP73831") (pin "4") (pinfunction "VIN_4") (pintype "power_in"))
      (node (ref "PFMF.050.1") (pin "2") (pinfunction "2_2") (pintype "passive"))
      (node (ref "Q1") (pin "1") (pinfunction "G_1") (pintype "bidirectional"))
      (node (ref "R1_PWRUSB") (pin "2") (pinfunction "2_2") (pintype "passive"))
      (node (ref "TP14") (pin "TP") (pinfunction "TP_TP") (pintype "input"))
    )
    (net (code "55") (name "VRTC") (class "Default")
      (node (ref "C11") (pin "1") (pinfunction "1_1") (pintype "passive"))
      (node (ref "C8") (pin "1") (pinfunction "1_1") (pintype "passive"))
      (node (ref "R_CAPACITOR") (pin "2") (pinfunction "2_2") (pintype "passive"))
      (node (ref "U3") (pin "14") (pinfunction "VBAT_14") (pintype "power_in"))
    )
    (net (code "56") (name "VUSB") (class "Default")
      (node (ref "J2") (pin "A4") (pinfunction "A4_A4") (pintype "bidirectional"))
      (node (ref "J2") (pin "A9") (pinfunction "A9_A9") (pintype "bidirectional"))
      (node (ref "J2") (pin "B4") (pinfunction "B4_B4") (pintype "bidirectional"))
      (node (ref "J2") (pin "B9") (pinfunction "B9_B9") (pintype "bidirectional"))
      (node (ref "PFMF.050.1") (pin "1") (pinfunction "1_1") (pintype "passive"))
    )
    (net (code "57") (name "unconnected-(IC1-NC-Pad4)") (class "Default")
      (node (ref "IC1") (pin "4") (pinfunction "NC_4") (pintype "no_connect"))
    )
    (net (code "58") (name "unconnected-(IC4-NC-Pad4)") (class "Default")
      (node (ref "IC4") (pin "4") (pinfunction "NC_4") (pintype "no_connect"))
    )
    (net (code "59") (name "unconnected-(J1-Pad1)") (class "Default")
      (node (ref "J1") (pin "1") (pinfunction "1_1") (pintype "bidirectional"))
    )
    (net (code "60") (name "unconnected-(J1-Pad6)") (class "Default")
      (node (ref "J1") (pin "6") (pinfunction "6_6") (pintype "bidirectional"))
    )
    (net (code "61") (name "unconnected-(J1-Pad7)") (class "Default")
      (node (ref "J1") (pin "7") (pinfunction "7_7") (pintype "bidirectional"))
    )
    (net (code "62") (name "unconnected-(J2-PadA8)") (class "Default")
      (node (ref "J2") (pin "A8") (pinfunction "A8_A8") (pintype "bidirectional"))
    )
    (net (code "63") (name "unconnected-(J2-PadB8)") (class "Default")
      (node (ref "J2") (pin "B8") (pinfunction "B8_B8") (pintype "bidirectional"))
    )
    (net (code "64") (name "unconnected-(J4-DAT1-PadP8)") (class "Default")
      (node (ref "J4") (pin "P8") (pinfunction "DAT1_P8") (pintype "bidirectional"))
    )
    (net (code "65") (name "unconnected-(J4-DAT2-PadP1)") (class "Default")
      (node (ref "J4") (pin "P1") (pinfunction "DAT2_P1") (pintype "bidirectional"))
    )
    (net (code "66") (name "unconnected-(J4-DETECTION_1-PadS1)") (class "Default")
      (node (ref "J4") (pin "S1") (pinfunction "DETECTION_1_S1") (pintype "bidirectional"))
    )
    (net (code "67") (name "unconnected-(J4-DETECTION_2-PadS2)") (class "Default")
      (node (ref "J4") (pin "S2") (pinfunction "DETECTION_2_S2") (pintype "bidirectional"))
    )
    (net (code "68") (name "unconnected-(U2-NC-Pad22)") (class "Default")
      (node (ref "U2") (pin "22") (pinfunction "NC_22") (pintype "no_connect"))
    )
    (net (code "69") (name "unconnected-(U4-~{ALERT}-Pad5)") (class "Default")
      (node (ref "U4") (pin "5") (pinfunction "~{ALERT}_5") (pintype "output"))
    )
  )
)
